# SC10033E1_4.net
KiCad netlist of a schematic drawn in Altium Designer
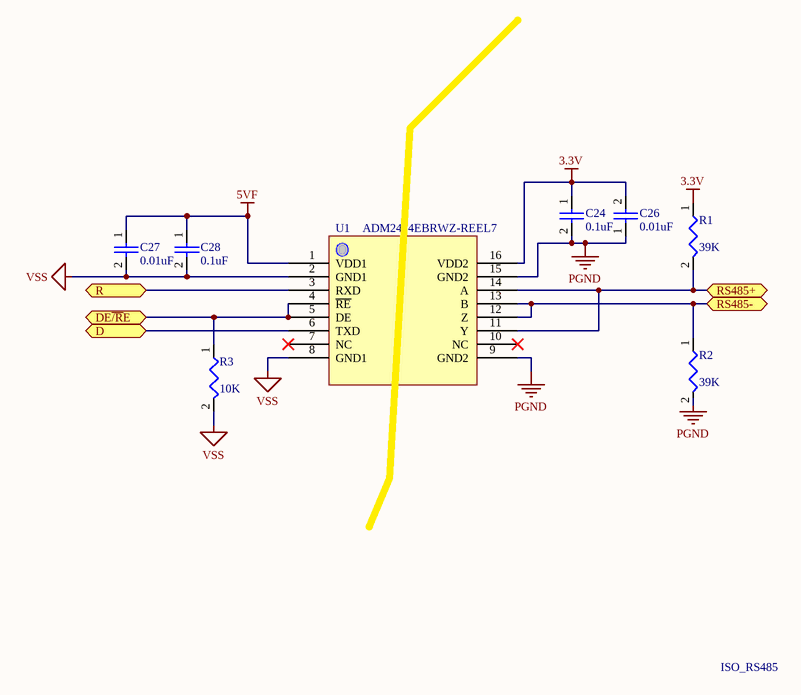
[diagram p0: SC10033E1_4.SchDoc]

(export (version "E")
  (design (tool "Eeschema 10.0.6"))
  (components
    (comp (ref "C24")
      (value "0.1uF")
      (footprint "C0805")
      (description "CAP SMD CR X7R 50V 10% 0.1uF 0805 ROHS")
      (fields (field (name "MANUFACTURER") "YAGEO") (field (name "Comment") "CAP"))
      (libsource (lib "enlogic") (part "CAP"))
    )
    (comp (ref "C26")
      (value "0.01uF")
      (footprint "C0805")
      (description "CAP SMD X7R 50V 10% 10nF 0805 ROHS")
      (fields (field (name "MANUFACTURER") "YAGEO") (field (name "Comment") "CAP"))
      (libsource (lib "enlogic") (part "CAP"))
    )
    (comp (ref "C27")
      (value "0.01uF")
      (footprint "C0805")
      (description "CAP SMD X7R 50V 10% 10nF 0805 ROHS")
      (fields (field (name "MANUFACTURER") "YAGEO") (field (name "Comment") "CAP"))
      (libsource (lib "enlogic") (part "CAP"))
    )
    (comp (ref "C28")
      (value "0.1uF")
      (footprint "C0805")
      (description "CAP SMD CR X7R 50V 10% 0.1uF 0805 ROHS")
      (fields (field (name "MANUFACTURER") "YAGEO") (field (name "Comment") "CAP"))
      (libsource (lib "enlogic") (part "CAP"))
    )
    (comp (ref "R1")
      (value "39K")
      (footprint "R0805")
      (description "RES THICK_FILM SMD 39K 5% 1/8W ROHS 0805")
      (fields (field (name "MANUFACTURER") "YAGEO") (field (name "Comment") "RES"))
      (libsource (lib "enlogic") (part "RES"))
    )
    (comp (ref "R2")
      (value "39K")
      (footprint "R0805")
      (description "RES THICK_FILM SMD 39K 5% 1/8W ROHS 0805")
      (fields (field (name "MANUFACTURER") "YAGEO") (field (name "Comment") "RES"))
      (libsource (lib "enlogic") (part "RES"))
    )
    (comp (ref "R3")
      (value "10K")
      (footprint "R0805")
      (description "RES THICK_FILM SMD 10K 5% 1/8W ROHS 0805")
      (fields (field (name "MANUFACTURER") "YAGEO") (field (name "Comment") "RES"))
      (libsource (lib "enlogic") (part "RES"))
    )
    (comp (ref "U1")
      (value "ADM2484EBRWZ-REEL7")
      (footprint "SOIC16")
      (description "IC Isolated, RS-485/RS-422 transceiver,5kV,SOIC16_W,ROHS")
      (fields (field (name "MANUFACTURER") "Analog Devices") (field (name "Comment") "ADM2484E"))
      (libsource (lib "enlogic") (part "ADM2484E"))
    )
  )
  (nets
    (net (code "1") (name "/D") (class "Default")
      (node (ref "U1") (pin "6") (pinfunction "TXD_6") (pintype "passive"))
    )
    (net (code "2") (name "/DE~{{slash}R}E") (class "Default")
      (node (ref "R3") (pin "1") (pinfunction "1_1") (pintype "passive"))
      (node (ref "U1") (pin "4") (pinfunction "~{RE}_4") (pintype "passive"))
      (node (ref "U1") (pin "5") (pinfunction "DE_5") (pintype "passive"))
    )
    (net (code "3") (name "/R") (class "Default")
      (node (ref "U1") (pin "3") (pinfunction "RXD_3") (pintype "passive"))
    )
    (net (code "4") (name "/RS485+") (class "Default")
      (node (ref "R1") (pin "2") (pinfunction "2_2") (pintype "passive"))
      (node (ref "U1") (pin "11") (pinfunction "Y_11") (pintype "passive"))
      (node (ref "U1") (pin "14") (pinfunction "A_14") (pintype "passive"))
    )
    (net (code "5") (name "/RS485-") (class "Default")
      (node (ref "R2") (pin "1") (pinfunction "1_1") (pintype "passive"))
      (node (ref "U1") (pin "12") (pinfunction "Z_12") (pintype "passive"))
      (node (ref "U1") (pin "13") (pinfunction "B_13") (pintype "passive"))
    )
    (net (code "6") (name "3.3V") (class "Default")
      (node (ref "C24") (pin "1") (pinfunction "1_1") (pintype "passive"))
      (node (ref "C26") (pin "2") (pinfunction "2_2") (pintype "passive"))
      (node (ref "R1") (pin "1") (pinfunction "1_1") (pintype "passive"))
      (node (ref "U1") (pin "16") (pinfunction "VDD2_16") (pintype "power_in"))
    )
    (net (code "7") (name "5VF") (class "Default")
      (node (ref "C27") (pin "1") (pinfunction "1_1") (pintype "passive"))
      (node (ref "C28") (pin "1") (pinfunction "1_1") (pintype "passive"))
      (node (ref "U1") (pin "1") (pinfunction "VDD1_1") (pintype "power_in"))
    )
    (net (code "8") (name "PGND") (class "Default")
      (node (ref "C24") (pin "2") (pinfunction "2_2") (pintype "passive"))
      (node (ref "C26") (pin "1") (pinfunction "1_1") (pintype "passive"))
      (node (ref "R2") (pin "2") (pinfunction "2_2") (pintype "passive"))
      (node (ref "U1") (pin "15") (pinfunction "GND2_15") (pintype "passive"))
      (node (ref "U1") (pin "9") (pinfunction "GND2_9") (pintype "power_in"))
    )
    (net (code "9") (name "VSS") (class "Default")
      (node (ref "C27") (pin "2") (pinfunction "2_2") (pintype "passive"))
      (node (ref "C28") (pin "2") (pinfunction "2_2") (pintype "passive"))
      (node (ref "R3") (pin "2") (pinfunction "2_2") (pintype "passive"))
      (node (ref "U1") (pin "2") (pinfunction "GND1_2") (pintype "passive"))
      (node (ref "U1") (pin "8") (pinfunction "GND1_8") (pintype "passive"))
    )
    (net (code "10") (name "unconnected-(U1-NC-Pad7)") (class "Default")
      (node (ref "U1") (pin "7") (pinfunction "NC_7") (pintype "power_in+no_connect"))
    )
    (net (code "11") (name "unconnected-(U1-NC-Pad10)") (class "Default")
      (node (ref "U1") (pin "10") (pinfunction "NC_10") (pintype "passive+no_connect"))
    )
  )
)
